# LED_Matrix_Controller.net
KiCad netlist of a schematic drawn in EAGLE
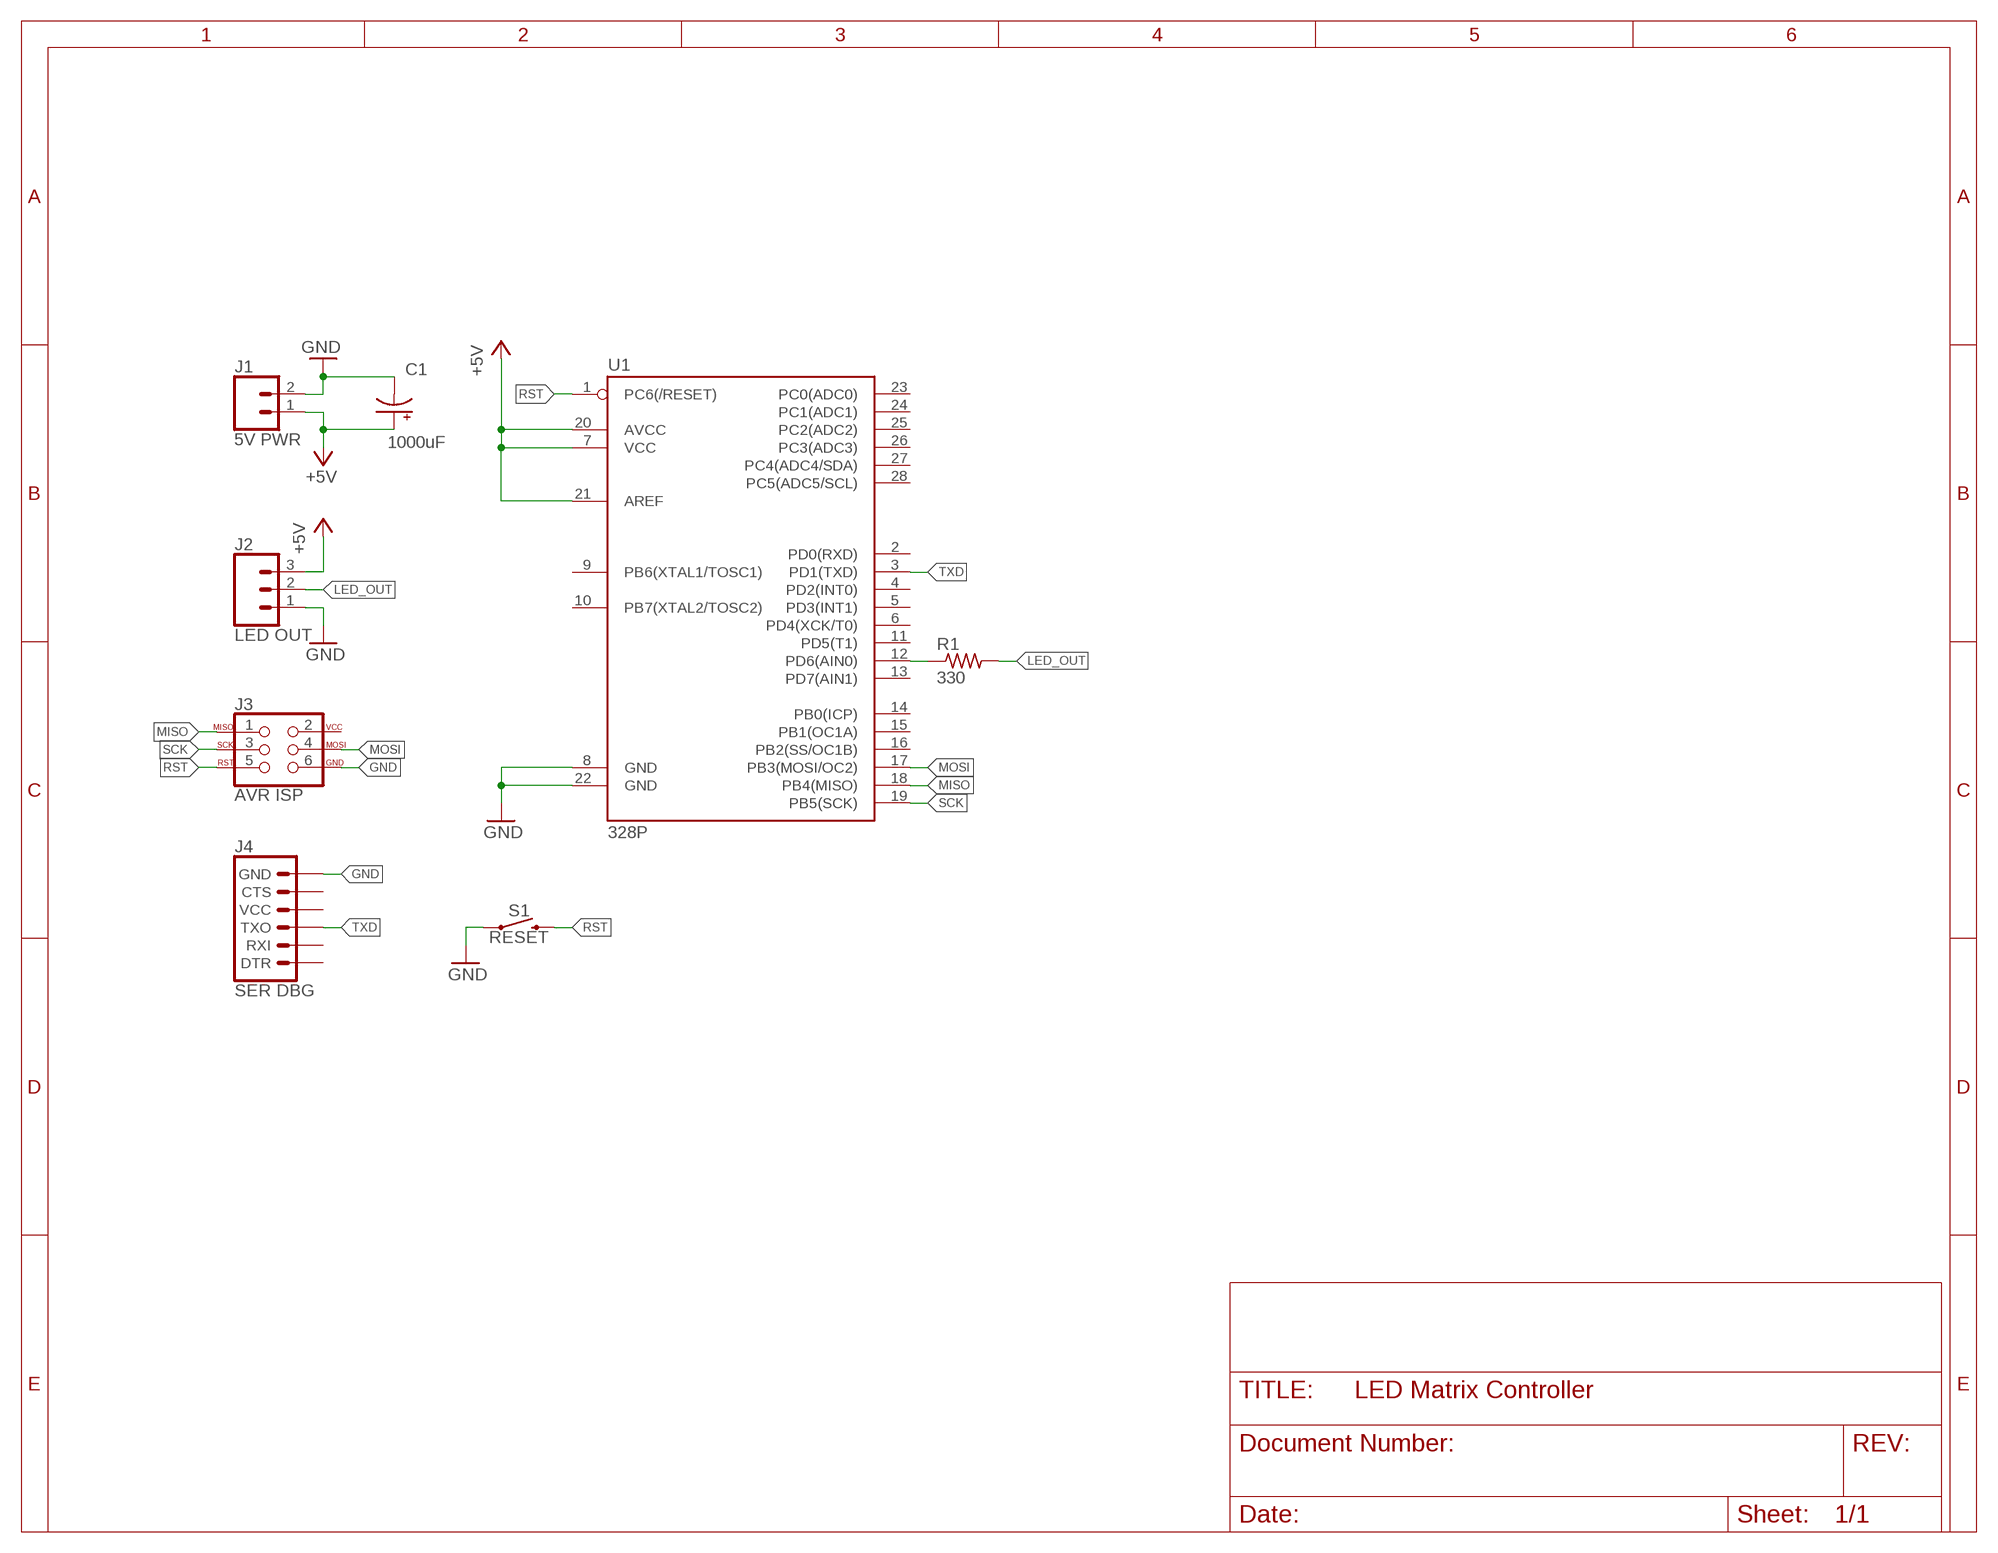
[diagram p0: schematic, sheet 1]

(export (version "E")
  (design (tool "Eeschema 10.0.6"))
  (components
    (comp (ref "C1")
      (value "1000uF")
      (footprint "eagle-import:E5-10,5")
      (libsource (lib "eagle-import") (part "CPOL-USE5-10.5"))
    )
    (comp (ref "J1")
      (value "5V PWR")
      (footprint "eagle-import:SCREWTERMINAL-5MM-2")
      (libsource (lib "eagle-import") (part "CONN_025MM"))
    )
    (comp (ref "J2")
      (value "LED OUT")
      (footprint "eagle-import:SCREWTERMINAL-5MM-3")
      (libsource (lib "eagle-import") (part "CONN_03-SCREW-5MM"))
    )
    (comp (ref "J3")
      (value "AVR ISP")
      (footprint "eagle-import:2X3")
      (libsource (lib "eagle-import") (part "AVR_SPI_PROG_3X2PTH"))
    )
    (comp (ref "J4")
      (value "SER DBG")
      (footprint "eagle-import:6_PIN_SERIAL_TARGET_SIDE_W_SILK")
      (libsource (lib "eagle-import") (part "6_PIN_SERIAL_TARGETSILK"))
    )
    (comp (ref "R1")
      (value "330")
      (footprint "eagle-import:0207_10")
      (libsource (lib "eagle-import") (part "R-US_0207/10"))
    )
    (comp (ref "S1")
      (value "RESET")
      (footprint "eagle-import:TACTILE_SWITCH_PTH_6.0MM")
      (libsource (lib "eagle-import") (part "MOMENTARY-SWITCH-SPST-PTH-6.0MM"))
    )
    (comp (ref "U1")
      (value "328P")
      (footprint "eagle-import:DIP28")
      (libsource (lib "eagle-import") (part "ATMEGA328P_PDIP"))
    )
  )
  (nets
    (net (code "1") (name "+5V") (class "Default")
      (node (ref "C1") (pin "+") (pinfunction "+_+") (pintype "passive"))
      (node (ref "J1") (pin "1") (pinfunction "1_1") (pintype "passive"))
      (node (ref "J2") (pin "3") (pinfunction "3_3") (pintype "passive"))
      (node (ref "U1") (pin "20") (pinfunction "AVCC_20") (pintype "bidirectional"))
      (node (ref "U1") (pin "21") (pinfunction "AREF_21") (pintype "bidirectional"))
      (node (ref "U1") (pin "7") (pinfunction "VCC_7") (pintype "bidirectional"))
    )
    (net (code "2") (name "GND") (class "Default")
      (node (ref "C1") (pin "-") (pinfunction "-_-") (pintype "passive"))
      (node (ref "J1") (pin "2") (pinfunction "2_2") (pintype "passive"))
      (node (ref "J2") (pin "1") (pinfunction "1_1") (pintype "passive"))
      (node (ref "J3") (pin "6") (pinfunction "6_6") (pintype "passive"))
      (node (ref "J4") (pin "P$6") (pinfunction "GND_P$6") (pintype "passive"))
      (node (ref "S1") (pin "1") (pinfunction "1_1") (pintype "passive"))
      (node (ref "U1") (pin "22") (pinfunction "GND_22") (pintype "bidirectional"))
      (node (ref "U1") (pin "8") (pinfunction "GND_8") (pintype "bidirectional"))
    )
    (net (code "3") (name "LED_OUT") (class "Default")
      (node (ref "J2") (pin "2") (pinfunction "2_2") (pintype "passive"))
      (node (ref "R1") (pin "2") (pinfunction "2_2") (pintype "passive"))
    )
    (net (code "4") (name "MISO") (class "Default")
      (node (ref "J3") (pin "1") (pinfunction "1_1") (pintype "passive"))
      (node (ref "U1") (pin "18") (pinfunction "PB4(MISO)_18") (pintype "bidirectional"))
    )
    (net (code "5") (name "MOSI") (class "Default")
      (node (ref "J3") (pin "4") (pinfunction "4_4") (pintype "passive"))
      (node (ref "U1") (pin "17") (pinfunction "PB3(MOSI/OC2)_17") (pintype "bidirectional"))
    )
    (net (code "6") (name "Net-(U1-PD6(AIN0))") (class "Default")
      (node (ref "R1") (pin "1") (pinfunction "1_1") (pintype "passive"))
      (node (ref "U1") (pin "12") (pinfunction "PD6(AIN0)_12") (pintype "bidirectional"))
    )
    (net (code "7") (name "RST") (class "Default")
      (node (ref "J3") (pin "5") (pinfunction "5_5") (pintype "passive"))
      (node (ref "S1") (pin "3") (pinfunction "2_3") (pintype "passive"))
      (node (ref "U1") (pin "1") (pinfunction "PC6(/RESET)_1") (pintype "bidirectional"))
    )
    (net (code "8") (name "SCK") (class "Default")
      (node (ref "J3") (pin "3") (pinfunction "3_3") (pintype "passive"))
      (node (ref "U1") (pin "19") (pinfunction "PB5(SCK)_19") (pintype "bidirectional"))
    )
    (net (code "9") (name "TXD") (class "Default")
      (node (ref "J4") (pin "P$2") (pinfunction "TXO_P$2") (pintype "passive"))
      (node (ref "U1") (pin "3") (pinfunction "PD1(TXD)_3") (pintype "bidirectional"))
    )
    (net (code "10") (name "unconnected-(J3-Pad2)") (class "Default")
      (node (ref "J3") (pin "2") (pinfunction "2_2") (pintype "passive"))
    )
    (net (code "11") (name "unconnected-(J4-CTS-PadP$5)") (class "Default")
      (node (ref "J4") (pin "P$5") (pinfunction "CTS_P$5") (pintype "passive"))
    )
    (net (code "12") (name "unconnected-(J4-DTR-PadP$1)") (class "Default")
      (node (ref "J4") (pin "P$1") (pinfunction "DTR_P$1") (pintype "passive"))
    )
    (net (code "13") (name "unconnected-(J4-RXI-PadP$3)") (class "Default")
      (node (ref "J4") (pin "P$3") (pinfunction "RXI_P$3") (pintype "passive"))
    )
    (net (code "14") (name "unconnected-(J4-VCC-PadP$4)") (class "Default")
      (node (ref "J4") (pin "P$4") (pinfunction "VCC_P$4") (pintype "passive"))
    )
    (net (code "15") (name "unconnected-(U1-PB0(ICP)-Pad14)") (class "Default")
      (node (ref "U1") (pin "14") (pinfunction "PB0(ICP)_14") (pintype "bidirectional"))
    )
    (net (code "16") (name "unconnected-(U1-PB1(OC1A)-Pad15)") (class "Default")
      (node (ref "U1") (pin "15") (pinfunction "PB1(OC1A)_15") (pintype "bidirectional"))
    )
    (net (code "17") (name "unconnected-(U1-PB2(SS{slash}OC1B)-Pad16)") (class "Default")
      (node (ref "U1") (pin "16") (pinfunction "PB2(SS/OC1B)_16") (pintype "bidirectional"))
    )
    (net (code "18") (name "unconnected-(U1-PB6(XTAL1{slash}TOSC1)-Pad9)") (class "Default")
      (node (ref "U1") (pin "9") (pinfunction "PB6(XTAL1/TOSC1)_9") (pintype "bidirectional"))
    )
    (net (code "19") (name "unconnected-(U1-PB7(XTAL2{slash}TOSC2)-Pad10)") (class "Default")
      (node (ref "U1") (pin "10") (pinfunction "PB7(XTAL2/TOSC2)_10") (pintype "bidirectional"))
    )
    (net (code "20") (name "unconnected-(U1-PC0(ADC0)-Pad23)") (class "Default")
      (node (ref "U1") (pin "23") (pinfunction "PC0(ADC0)_23") (pintype "bidirectional"))
    )
    (net (code "21") (name "unconnected-(U1-PC1(ADC1)-Pad24)") (class "Default")
      (node (ref "U1") (pin "24") (pinfunction "PC1(ADC1)_24") (pintype "bidirectional"))
    )
    (net (code "22") (name "unconnected-(U1-PC2(ADC2)-Pad25)") (class "Default")
      (node (ref "U1") (pin "25") (pinfunction "PC2(ADC2)_25") (pintype "bidirectional"))
    )
    (net (code "23") (name "unconnected-(U1-PC3(ADC3)-Pad26)") (class "Default")
      (node (ref "U1") (pin "26") (pinfunction "PC3(ADC3)_26") (pintype "bidirectional"))
    )
    (net (code "24") (name "unconnected-(U1-PC4(ADC4{slash}SDA)-Pad27)") (class "Default")
      (node (ref "U1") (pin "27") (pinfunction "PC4(ADC4/SDA)_27") (pintype "bidirectional"))
    )
    (net (code "25") (name "unconnected-(U1-PC5(ADC5{slash}SCL)-Pad28)") (class "Default")
      (node (ref "U1") (pin "28") (pinfunction "PC5(ADC5/SCL)_28") (pintype "bidirectional"))
    )
    (net (code "26") (name "unconnected-(U1-PD0(RXD)-Pad2)") (class "Default")
      (node (ref "U1") (pin "2") (pinfunction "PD0(RXD)_2") (pintype "bidirectional"))
    )
    (net (code "27") (name "unconnected-(U1-PD2(INT0)-Pad4)") (class "Default")
      (node (ref "U1") (pin "4") (pinfunction "PD2(INT0)_4") (pintype "bidirectional"))
    )
    (net (code "28") (name "unconnected-(U1-PD3(INT1)-Pad5)") (class "Default")
      (node (ref "U1") (pin "5") (pinfunction "PD3(INT1)_5") (pintype "bidirectional"))
    )
    (net (code "29") (name "unconnected-(U1-PD4(XCK{slash}T0)-Pad6)") (class "Default")
      (node (ref "U1") (pin "6") (pinfunction "PD4(XCK/T0)_6") (pintype "bidirectional"))
    )
    (net (code "30") (name "unconnected-(U1-PD5(T1)-Pad11)") (class "Default")
      (node (ref "U1") (pin "11") (pinfunction "PD5(T1)_11") (pintype "bidirectional"))
    )
    (net (code "31") (name "unconnected-(U1-PD7(AIN1)-Pad13)") (class "Default")
      (node (ref "U1") (pin "13") (pinfunction "PD7(AIN1)_13") (pintype "bidirectional"))
    )
  )
)
